# Token2.net
KiCad netlist of a schematic drawn in EAGLE
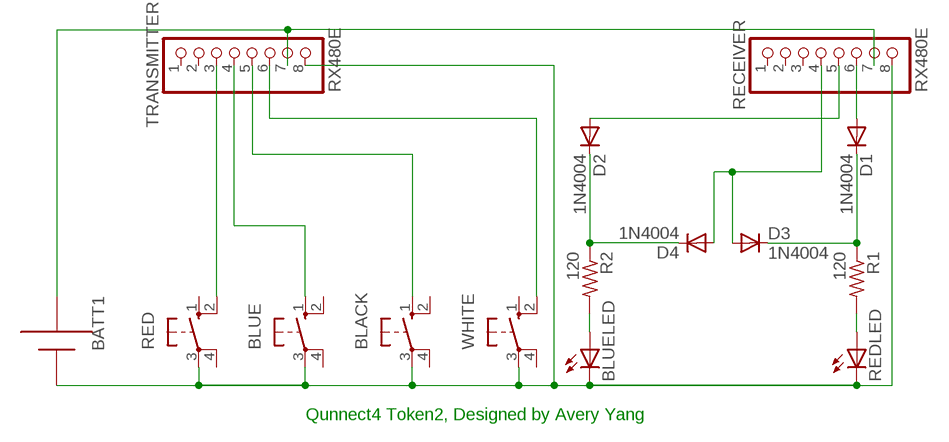
[diagram p0: schematic, sheet 1]

(export (version "E")
  (design (tool "Eeschema 10.0.6"))
  (components
    (comp (ref "BATT1")
      (value "AAA")
      (footprint "eagle-import:12BH412")
      (libsource (lib "eagle-import") (part "AAA"))
    )
    (comp (ref "BLACK")
      (value "10-XX")
      (footprint "eagle-import:B3F-10XX")
      (fields (field (name "MPN") "B3F-1000"))
      (libsource (lib "eagle-import") (part "10-XX"))
    )
    (comp (ref "BLUE")
      (value "10-XX")
      (footprint "eagle-import:B3F-10XX")
      (fields (field (name "MPN") "B3F-1000"))
      (libsource (lib "eagle-import") (part "10-XX"))
    )
    (comp (ref "BLUELED")
      (value "LED5MM")
      (footprint "eagle-import:LED5MM")
      (libsource (lib "eagle-import") (part "LED5MM"))
    )
    (comp (ref "D1")
      (value "1N4004")
      (footprint "eagle-import:DO41-10")
      (libsource (lib "eagle-import") (part "1N4004"))
    )
    (comp (ref "D2")
      (value "1N4004")
      (footprint "eagle-import:DO41-10")
      (libsource (lib "eagle-import") (part "1N4004"))
    )
    (comp (ref "D3")
      (value "1N4004")
      (footprint "eagle-import:DO41-10")
      (libsource (lib "eagle-import") (part "1N4004"))
    )
    (comp (ref "D4")
      (value "1N4004")
      (footprint "eagle-import:DO41-10")
      (libsource (lib "eagle-import") (part "1N4004"))
    )
    (comp (ref "R1")
      (value "120")
      (footprint "eagle-import:0207_10")
      (libsource (lib "eagle-import") (part "R-US_0207/10"))
    )
    (comp (ref "R2")
      (value "120")
      (footprint "eagle-import:0207_10")
      (libsource (lib "eagle-import") (part "R-US_0207/10"))
    )
    (comp (ref "RECEIVER")
      (value "RX480E")
      (footprint "eagle-import:1X08")
      (libsource (lib "eagle-import") (part "PINHD-1X8"))
    )
    (comp (ref "RED")
      (value "10-XX")
      (footprint "eagle-import:B3F-10XX")
      (fields (field (name "MPN") "B3F-1000"))
      (libsource (lib "eagle-import") (part "10-XX"))
    )
    (comp (ref "REDLED")
      (value "LED5MM")
      (footprint "eagle-import:LED5MM")
      (libsource (lib "eagle-import") (part "LED5MM"))
    )
    (comp (ref "TRANSMITTER")
      (value "RX480E")
      (footprint "eagle-import:1X08")
      (libsource (lib "eagle-import") (part "PINHD-1X8"))
    )
    (comp (ref "WHITE")
      (value "10-XX")
      (footprint "eagle-import:B3F-10XX")
      (fields (field (name "MPN") "B3F-1000"))
      (libsource (lib "eagle-import") (part "10-XX"))
    )
  )
  (nets
    (net (code "1") (name "Net-(BATT1-Pad-)") (class "Default")
      (node (ref "BATT1") (pin "-") (pinfunction "-_-") (pintype "bidirectional"))
      (node (ref "RECEIVER") (pin "7") (pinfunction "7_7") (pintype "passive"))
      (node (ref "TRANSMITTER") (pin "7") (pinfunction "7_7") (pintype "passive"))
    )
    (net (code "2") (name "Net-(BLACK-P)") (class "Default")
      (node (ref "BATT1") (pin "+") (pinfunction "+_+") (pintype "bidirectional"))
      (node (ref "BLACK") (pin "3") (pinfunction "P_3") (pintype "passive"))
      (node (ref "BLUE") (pin "3") (pinfunction "P_3") (pintype "passive"))
      (node (ref "BLUELED") (pin "K") (pinfunction "C_K") (pintype "passive"))
      (node (ref "RECEIVER") (pin "8") (pinfunction "8_8") (pintype "passive"))
      (node (ref "RED") (pin "3") (pinfunction "P_3") (pintype "passive"))
      (node (ref "REDLED") (pin "K") (pinfunction "C_K") (pintype "passive"))
      (node (ref "TRANSMITTER") (pin "8") (pinfunction "8_8") (pintype "passive"))
      (node (ref "WHITE") (pin "3") (pinfunction "P_3") (pintype "passive"))
    )
    (net (code "3") (name "Net-(BLACK-S)") (class "Default")
      (node (ref "BLACK") (pin "1") (pinfunction "S_1") (pintype "passive"))
      (node (ref "TRANSMITTER") (pin "5") (pinfunction "5_5") (pintype "passive"))
    )
    (net (code "4") (name "Net-(BLUE-S)") (class "Default")
      (node (ref "BLUE") (pin "1") (pinfunction "S_1") (pintype "passive"))
      (node (ref "TRANSMITTER") (pin "4") (pinfunction "4_4") (pintype "passive"))
    )
    (net (code "5") (name "Net-(BLUELED-PadA)") (class "Default")
      (node (ref "BLUELED") (pin "A") (pinfunction "A_A") (pintype "passive"))
      (node (ref "R2") (pin "2") (pinfunction "2_2") (pintype "passive"))
    )
    (net (code "6") (name "Net-(D1-PadA)") (class "Default")
      (node (ref "D1") (pin "A") (pinfunction "A_A") (pintype "passive"))
      (node (ref "RECEIVER") (pin "6") (pinfunction "6_6") (pintype "passive"))
    )
    (net (code "7") (name "Net-(D1-PadC)") (class "Default")
      (node (ref "D1") (pin "C") (pinfunction "C_C") (pintype "passive"))
      (node (ref "D3") (pin "C") (pinfunction "C_C") (pintype "passive"))
      (node (ref "R1") (pin "1") (pinfunction "1_1") (pintype "passive"))
    )
    (net (code "8") (name "Net-(D2-PadA)") (class "Default")
      (node (ref "D2") (pin "A") (pinfunction "A_A") (pintype "passive"))
      (node (ref "RECEIVER") (pin "5") (pinfunction "5_5") (pintype "passive"))
    )
    (net (code "9") (name "Net-(D2-PadC)") (class "Default")
      (node (ref "D2") (pin "C") (pinfunction "C_C") (pintype "passive"))
      (node (ref "D4") (pin "C") (pinfunction "C_C") (pintype "passive"))
      (node (ref "R2") (pin "1") (pinfunction "1_1") (pintype "passive"))
    )
    (net (code "10") (name "Net-(D3-PadA)") (class "Default")
      (node (ref "D3") (pin "A") (pinfunction "A_A") (pintype "passive"))
      (node (ref "D4") (pin "A") (pinfunction "A_A") (pintype "passive"))
      (node (ref "RECEIVER") (pin "4") (pinfunction "4_4") (pintype "passive"))
    )
    (net (code "11") (name "Net-(R1-Pad2)") (class "Default")
      (node (ref "R1") (pin "2") (pinfunction "2_2") (pintype "passive"))
      (node (ref "REDLED") (pin "A") (pinfunction "A_A") (pintype "passive"))
    )
    (net (code "12") (name "Net-(RED-S1)") (class "Default")
      (node (ref "RED") (pin "2") (pinfunction "S1_2") (pintype "passive"))
      (node (ref "TRANSMITTER") (pin "3") (pinfunction "3_3") (pintype "passive"))
    )
    (net (code "13") (name "Net-(WHITE-S1)") (class "Default")
      (node (ref "TRANSMITTER") (pin "6") (pinfunction "6_6") (pintype "passive"))
      (node (ref "WHITE") (pin "2") (pinfunction "S1_2") (pintype "passive"))
    )
    (net (code "14") (name "unconnected-(BLACK-P1-Pad4)") (class "Default")
      (node (ref "BLACK") (pin "4") (pinfunction "P1_4") (pintype "passive"))
    )
    (net (code "15") (name "unconnected-(BLACK-S1-Pad2)") (class "Default")
      (node (ref "BLACK") (pin "2") (pinfunction "S1_2") (pintype "passive"))
    )
    (net (code "16") (name "unconnected-(BLUE-P1-Pad4)") (class "Default")
      (node (ref "BLUE") (pin "4") (pinfunction "P1_4") (pintype "passive"))
    )
    (net (code "17") (name "unconnected-(BLUE-S1-Pad2)") (class "Default")
      (node (ref "BLUE") (pin "2") (pinfunction "S1_2") (pintype "passive"))
    )
    (net (code "18") (name "unconnected-(RECEIVER-Pad1)") (class "Default")
      (node (ref "RECEIVER") (pin "1") (pinfunction "1_1") (pintype "passive"))
    )
    (net (code "19") (name "unconnected-(RECEIVER-Pad2)") (class "Default")
      (node (ref "RECEIVER") (pin "2") (pinfunction "2_2") (pintype "passive"))
    )
    (net (code "20") (name "unconnected-(RECEIVER-Pad3)") (class "Default")
      (node (ref "RECEIVER") (pin "3") (pinfunction "3_3") (pintype "passive"))
    )
    (net (code "21") (name "unconnected-(RED-P1-Pad4)") (class "Default")
      (node (ref "RED") (pin "4") (pinfunction "P1_4") (pintype "passive"))
    )
    (net (code "22") (name "unconnected-(RED-S-Pad1)") (class "Default")
      (node (ref "RED") (pin "1") (pinfunction "S_1") (pintype "passive"))
    )
    (net (code "23") (name "unconnected-(TRANSMITTER-Pad1)") (class "Default")
      (node (ref "TRANSMITTER") (pin "1") (pinfunction "1_1") (pintype "passive"))
    )
    (net (code "24") (name "unconnected-(TRANSMITTER-Pad2)") (class "Default")
      (node (ref "TRANSMITTER") (pin "2") (pinfunction "2_2") (pintype "passive"))
    )
    (net (code "25") (name "unconnected-(WHITE-P1-Pad4)") (class "Default")
      (node (ref "WHITE") (pin "4") (pinfunction "P1_4") (pintype "passive"))
    )
    (net (code "26") (name "unconnected-(WHITE-S-Pad1)") (class "Default")
      (node (ref "WHITE") (pin "1") (pinfunction "S_1") (pintype "passive"))
    )
  )
)
